# matrix_schematic.net
KiCad netlist of a schematic drawn in EAGLE
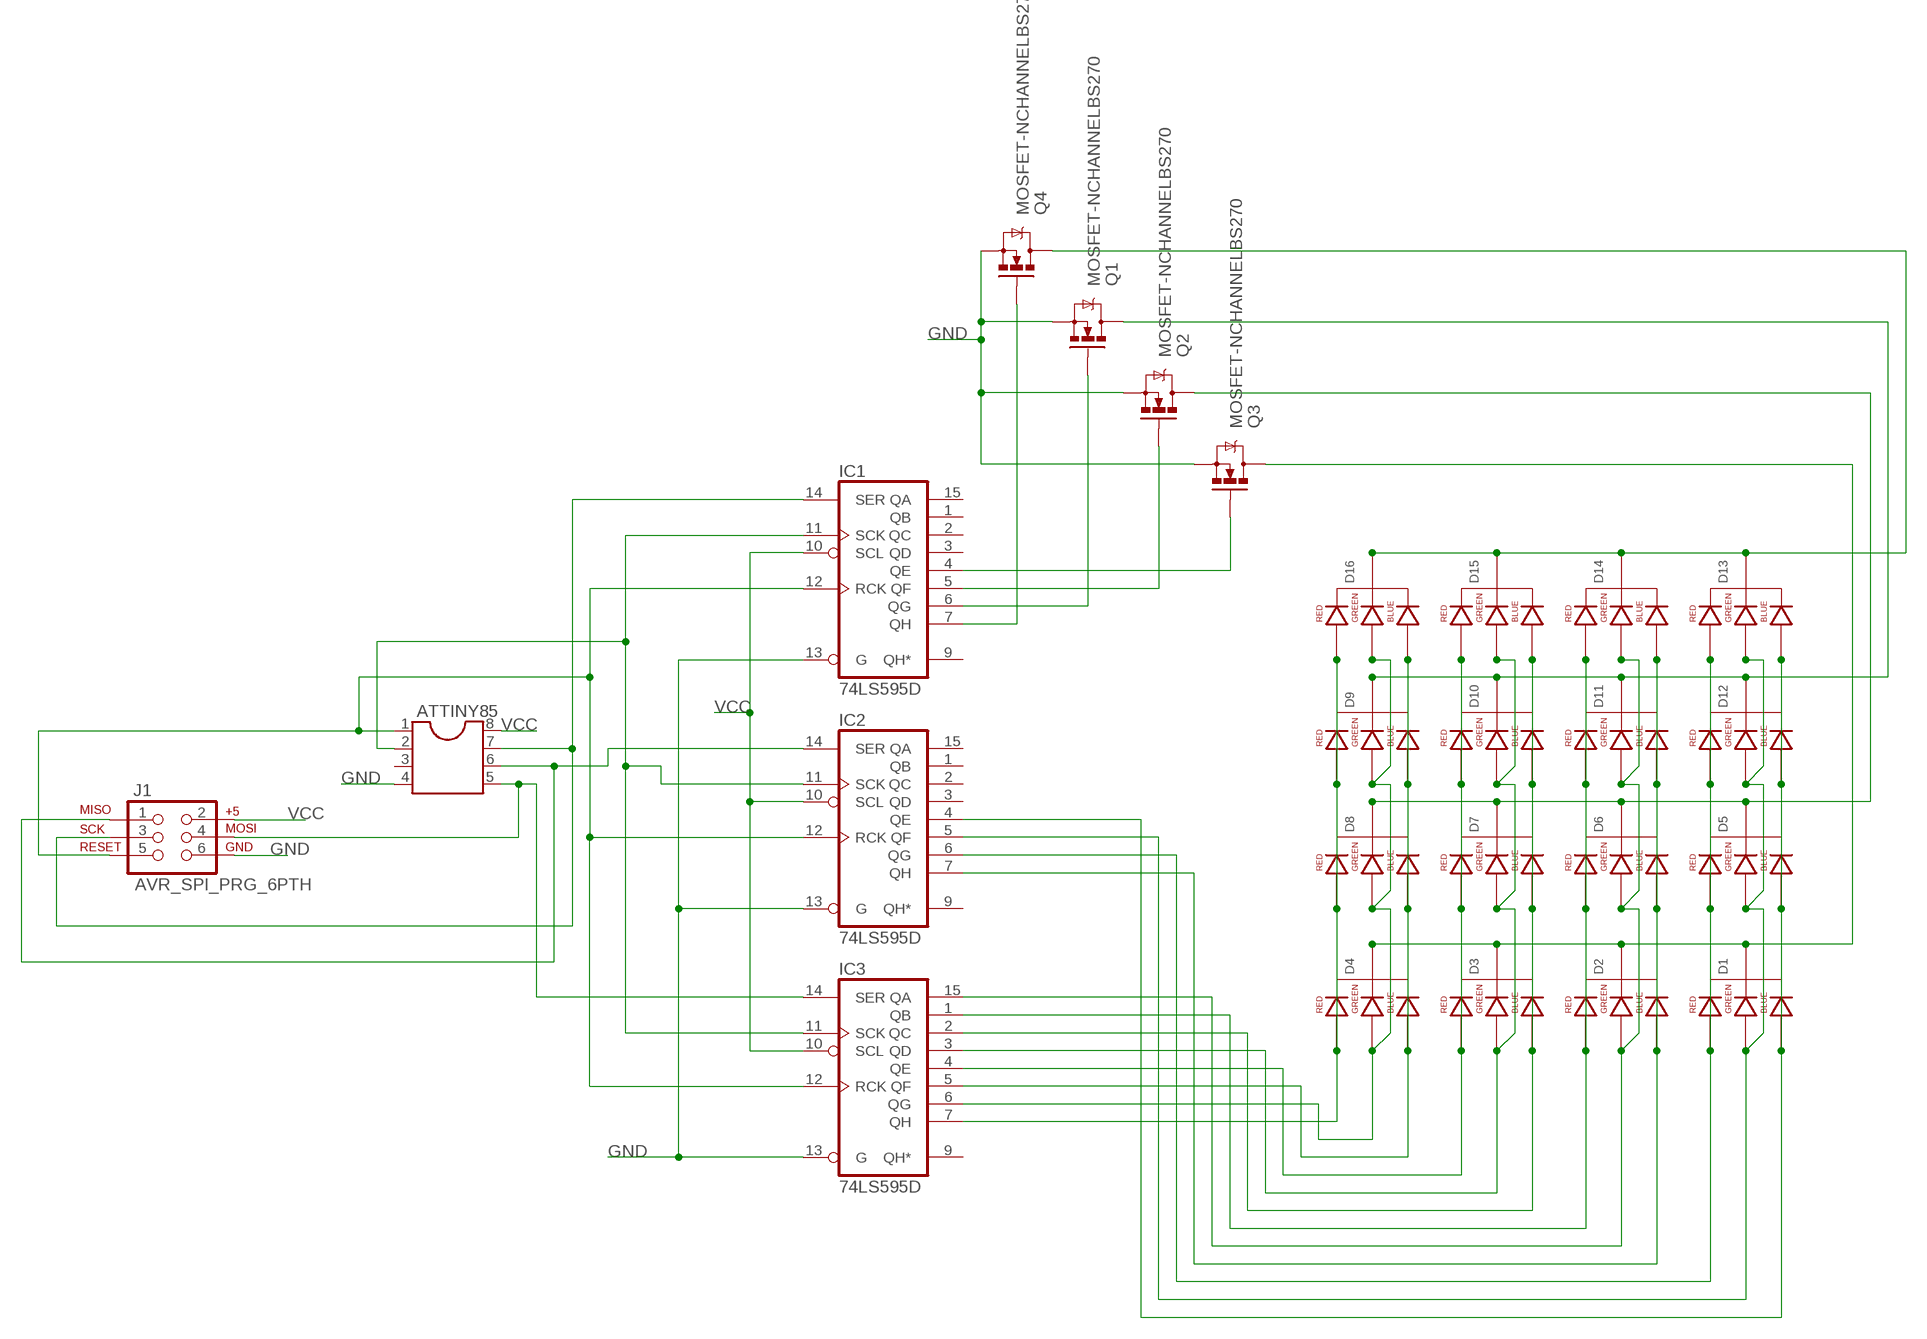
[diagram p0: schematic, sheet 1]

(export (version "E")
  (design (tool "Eeschema 10.0.6"))
  (components
    (comp (ref "ATTINY85")
      (value "DIL8")
      (footprint "eagle-import:DIL08")
      (libsource (lib "eagle-import") (part "DIL8"))
    )
    (comp (ref "D1")
      (value "LED-RGB-CC-THRUDIFFUSE")
      (footprint "eagle-import:LED-RGB-THRU")
      (libsource (lib "eagle-import") (part "LED-RGB-CC-THRUDIFFUSE"))
    )
    (comp (ref "D2")
      (value "LED-RGB-CC-THRUDIFFUSE")
      (footprint "eagle-import:LED-RGB-THRU")
      (libsource (lib "eagle-import") (part "LED-RGB-CC-THRUDIFFUSE"))
    )
    (comp (ref "D3")
      (value "LED-RGB-CC-THRUDIFFUSE")
      (footprint "eagle-import:LED-RGB-THRU")
      (libsource (lib "eagle-import") (part "LED-RGB-CC-THRUDIFFUSE"))
    )
    (comp (ref "D4")
      (value "LED-RGB-CC-THRUDIFFUSE")
      (footprint "eagle-import:LED-RGB-THRU")
      (libsource (lib "eagle-import") (part "LED-RGB-CC-THRUDIFFUSE"))
    )
    (comp (ref "D5")
      (value "LED-RGB-CC-THRUDIFFUSE")
      (footprint "eagle-import:LED-RGB-THRU")
      (libsource (lib "eagle-import") (part "LED-RGB-CC-THRUDIFFUSE"))
    )
    (comp (ref "D6")
      (value "LED-RGB-CC-THRUDIFFUSE")
      (footprint "eagle-import:LED-RGB-THRU")
      (libsource (lib "eagle-import") (part "LED-RGB-CC-THRUDIFFUSE"))
    )
    (comp (ref "D7")
      (value "LED-RGB-CC-THRUDIFFUSE")
      (footprint "eagle-import:LED-RGB-THRU")
      (libsource (lib "eagle-import") (part "LED-RGB-CC-THRUDIFFUSE"))
    )
    (comp (ref "D8")
      (value "LED-RGB-CC-THRUDIFFUSE")
      (footprint "eagle-import:LED-RGB-THRU")
      (libsource (lib "eagle-import") (part "LED-RGB-CC-THRUDIFFUSE"))
    )
    (comp (ref "D9")
      (value "LED-RGB-CC-THRUDIFFUSE")
      (footprint "eagle-import:LED-RGB-THRU")
      (libsource (lib "eagle-import") (part "LED-RGB-CC-THRUDIFFUSE"))
    )
    (comp (ref "D10")
      (value "LED-RGB-CC-THRUDIFFUSE")
      (footprint "eagle-import:LED-RGB-THRU")
      (libsource (lib "eagle-import") (part "LED-RGB-CC-THRUDIFFUSE"))
    )
    (comp (ref "D11")
      (value "LED-RGB-CC-THRUDIFFUSE")
      (footprint "eagle-import:LED-RGB-THRU")
      (libsource (lib "eagle-import") (part "LED-RGB-CC-THRUDIFFUSE"))
    )
    (comp (ref "D12")
      (value "LED-RGB-CC-THRUDIFFUSE")
      (footprint "eagle-import:LED-RGB-THRU")
      (libsource (lib "eagle-import") (part "LED-RGB-CC-THRUDIFFUSE"))
    )
    (comp (ref "D13")
      (value "LED-RGB-CC-THRUDIFFUSE")
      (footprint "eagle-import:LED-RGB-THRU")
      (libsource (lib "eagle-import") (part "LED-RGB-CC-THRUDIFFUSE"))
    )
    (comp (ref "D14")
      (value "LED-RGB-CC-THRUDIFFUSE")
      (footprint "eagle-import:LED-RGB-THRU")
      (libsource (lib "eagle-import") (part "LED-RGB-CC-THRUDIFFUSE"))
    )
    (comp (ref "D15")
      (value "LED-RGB-CC-THRUDIFFUSE")
      (footprint "eagle-import:LED-RGB-THRU")
      (libsource (lib "eagle-import") (part "LED-RGB-CC-THRUDIFFUSE"))
    )
    (comp (ref "D16")
      (value "LED-RGB-CC-THRUDIFFUSE")
      (footprint "eagle-import:LED-RGB-THRU")
      (libsource (lib "eagle-import") (part "LED-RGB-CC-THRUDIFFUSE"))
    )
    (comp (ref "IC1")
      (value "74LS595D")
      (footprint "eagle-import:SO16")
      (libsource (lib "eagle-import") (part "74595DLS"))
    )
    (comp (ref "IC2")
      (value "74LS595D")
      (footprint "eagle-import:SO16")
      (libsource (lib "eagle-import") (part "74595DLS"))
    )
    (comp (ref "IC3")
      (value "74LS595D")
      (footprint "eagle-import:SO16")
      (libsource (lib "eagle-import") (part "74595DLS"))
    )
    (comp (ref "J1")
      (value "AVR_SPI_PRG_6PTH")
      (footprint "eagle-import:2X3")
      (libsource (lib "eagle-import") (part "AVR_SPI_PRG_6PTH"))
    )
    (comp (ref "Q1")
      (value "MOSFET-NCHANNELBS270")
      (footprint "eagle-import:TO-92")
      (libsource (lib "eagle-import") (part "MOSFET-NCHANNELBS170"))
    )
    (comp (ref "Q2")
      (value "MOSFET-NCHANNELBS270")
      (footprint "eagle-import:TO-92")
      (libsource (lib "eagle-import") (part "MOSFET-NCHANNELBS170"))
    )
    (comp (ref "Q3")
      (value "MOSFET-NCHANNELBS270")
      (footprint "eagle-import:TO-92")
      (libsource (lib "eagle-import") (part "MOSFET-NCHANNELBS170"))
    )
    (comp (ref "Q4")
      (value "MOSFET-NCHANNELBS270")
      (footprint "eagle-import:TO-92")
      (libsource (lib "eagle-import") (part "MOSFET-NCHANNELBS170"))
    )
  )
  (nets
    (net (code "1") (name "/GND") (class "Default")
      (node (ref "ATTINY85") (pin "4") (pinfunction "4_4") (pintype "passive"))
      (node (ref "IC1") (pin "13") (pinfunction "G_13") (pintype "input"))
      (node (ref "IC2") (pin "13") (pinfunction "G_13") (pintype "input"))
      (node (ref "IC3") (pin "13") (pinfunction "G_13") (pintype "input"))
      (node (ref "J1") (pin "6") (pinfunction "6_6") (pintype "passive"))
      (node (ref "Q1") (pin "3") (pinfunction "S_3") (pintype "passive"))
      (node (ref "Q2") (pin "3") (pinfunction "S_3") (pintype "passive"))
      (node (ref "Q3") (pin "3") (pinfunction "S_3") (pintype "passive"))
      (node (ref "Q4") (pin "3") (pinfunction "S_3") (pintype "passive"))
    )
    (net (code "2") (name "/VCC") (class "Default")
      (node (ref "ATTINY85") (pin "8") (pinfunction "8_8") (pintype "passive"))
      (node (ref "IC1") (pin "10") (pinfunction "SCL_10") (pintype "input"))
      (node (ref "IC2") (pin "10") (pinfunction "SCL_10") (pintype "input"))
      (node (ref "IC3") (pin "10") (pinfunction "SCL_10") (pintype "input"))
      (node (ref "J1") (pin "2") (pinfunction "2_2") (pintype "passive"))
    )
    (net (code "3") (name "Net-(D1-BLUE_CATHODE)") (class "Default")
      (node (ref "D1") (pin "4") (pinfunction "BLUE_CATHODE_4") (pintype "bidirectional"))
      (node (ref "D12") (pin "4") (pinfunction "BLUE_CATHODE_4") (pintype "bidirectional"))
      (node (ref "D13") (pin "4") (pinfunction "BLUE_CATHODE_4") (pintype "bidirectional"))
      (node (ref "D5") (pin "4") (pinfunction "BLUE_CATHODE_4") (pintype "bidirectional"))
      (node (ref "IC2") (pin "4") (pinfunction "QE_4") (pintype "tri_state"))
    )
    (net (code "4") (name "Net-(D1-CATHODE)") (class "Default")
      (node (ref "D1") (pin "2") (pinfunction "CATHODE_2") (pintype "bidirectional"))
      (node (ref "D2") (pin "2") (pinfunction "CATHODE_2") (pintype "bidirectional"))
      (node (ref "D3") (pin "2") (pinfunction "CATHODE_2") (pintype "bidirectional"))
      (node (ref "D4") (pin "2") (pinfunction "CATHODE_2") (pintype "bidirectional"))
      (node (ref "Q3") (pin "1") (pinfunction "D_1") (pintype "passive"))
    )
    (net (code "5") (name "Net-(D1-GREEN_CATHODE)") (class "Default")
      (node (ref "D1") (pin "3") (pinfunction "GREEN_CATHODE_3") (pintype "bidirectional"))
      (node (ref "D12") (pin "3") (pinfunction "GREEN_CATHODE_3") (pintype "bidirectional"))
      (node (ref "D13") (pin "3") (pinfunction "GREEN_CATHODE_3") (pintype "bidirectional"))
      (node (ref "D5") (pin "3") (pinfunction "GREEN_CATHODE_3") (pintype "bidirectional"))
      (node (ref "IC2") (pin "5") (pinfunction "QF_5") (pintype "tri_state"))
    )
    (net (code "6") (name "Net-(D1-RED_CATHODE)") (class "Default")
      (node (ref "D1") (pin "1") (pinfunction "RED_CATHODE_1") (pintype "bidirectional"))
      (node (ref "D12") (pin "1") (pinfunction "RED_CATHODE_1") (pintype "bidirectional"))
      (node (ref "D13") (pin "1") (pinfunction "RED_CATHODE_1") (pintype "bidirectional"))
      (node (ref "D5") (pin "1") (pinfunction "RED_CATHODE_1") (pintype "bidirectional"))
      (node (ref "IC2") (pin "6") (pinfunction "QG_6") (pintype "tri_state"))
    )
    (net (code "7") (name "Net-(D5-CATHODE)") (class "Default")
      (node (ref "D5") (pin "2") (pinfunction "CATHODE_2") (pintype "bidirectional"))
      (node (ref "D6") (pin "2") (pinfunction "CATHODE_2") (pintype "bidirectional"))
      (node (ref "D7") (pin "2") (pinfunction "CATHODE_2") (pintype "bidirectional"))
      (node (ref "D8") (pin "2") (pinfunction "CATHODE_2") (pintype "bidirectional"))
      (node (ref "Q2") (pin "1") (pinfunction "D_1") (pintype "passive"))
    )
    (net (code "8") (name "Net-(D10-BLUE_CATHODE)") (class "Default")
      (node (ref "D10") (pin "4") (pinfunction "BLUE_CATHODE_4") (pintype "bidirectional"))
      (node (ref "D15") (pin "4") (pinfunction "BLUE_CATHODE_4") (pintype "bidirectional"))
      (node (ref "D3") (pin "4") (pinfunction "BLUE_CATHODE_4") (pintype "bidirectional"))
      (node (ref "D7") (pin "4") (pinfunction "BLUE_CATHODE_4") (pintype "bidirectional"))
      (node (ref "IC3") (pin "2") (pinfunction "QC_2") (pintype "tri_state"))
    )
    (net (code "9") (name "Net-(D10-CATHODE)") (class "Default")
      (node (ref "D10") (pin "2") (pinfunction "CATHODE_2") (pintype "bidirectional"))
      (node (ref "D11") (pin "2") (pinfunction "CATHODE_2") (pintype "bidirectional"))
      (node (ref "D12") (pin "2") (pinfunction "CATHODE_2") (pintype "bidirectional"))
      (node (ref "D9") (pin "2") (pinfunction "CATHODE_2") (pintype "bidirectional"))
      (node (ref "Q1") (pin "1") (pinfunction "D_1") (pintype "passive"))
    )
    (net (code "10") (name "Net-(D10-GREEN_CATHODE)") (class "Default")
      (node (ref "D10") (pin "3") (pinfunction "GREEN_CATHODE_3") (pintype "bidirectional"))
      (node (ref "D15") (pin "3") (pinfunction "GREEN_CATHODE_3") (pintype "bidirectional"))
      (node (ref "D3") (pin "3") (pinfunction "GREEN_CATHODE_3") (pintype "bidirectional"))
      (node (ref "D7") (pin "3") (pinfunction "GREEN_CATHODE_3") (pintype "bidirectional"))
      (node (ref "IC3") (pin "3") (pinfunction "QD_3") (pintype "tri_state"))
    )
    (net (code "11") (name "Net-(D10-RED_CATHODE)") (class "Default")
      (node (ref "D10") (pin "1") (pinfunction "RED_CATHODE_1") (pintype "bidirectional"))
      (node (ref "D15") (pin "1") (pinfunction "RED_CATHODE_1") (pintype "bidirectional"))
      (node (ref "D3") (pin "1") (pinfunction "RED_CATHODE_1") (pintype "bidirectional"))
      (node (ref "D7") (pin "1") (pinfunction "RED_CATHODE_1") (pintype "bidirectional"))
      (node (ref "IC3") (pin "4") (pinfunction "QE_4") (pintype "tri_state"))
    )
    (net (code "12") (name "Net-(D11-BLUE_CATHODE)") (class "Default")
      (node (ref "D11") (pin "4") (pinfunction "BLUE_CATHODE_4") (pintype "bidirectional"))
      (node (ref "D14") (pin "4") (pinfunction "BLUE_CATHODE_4") (pintype "bidirectional"))
      (node (ref "D2") (pin "4") (pinfunction "BLUE_CATHODE_4") (pintype "bidirectional"))
      (node (ref "D6") (pin "4") (pinfunction "BLUE_CATHODE_4") (pintype "bidirectional"))
      (node (ref "IC2") (pin "7") (pinfunction "QH_7") (pintype "tri_state"))
    )
    (net (code "13") (name "Net-(D11-GREEN_CATHODE)") (class "Default")
      (node (ref "D11") (pin "3") (pinfunction "GREEN_CATHODE_3") (pintype "bidirectional"))
      (node (ref "D14") (pin "3") (pinfunction "GREEN_CATHODE_3") (pintype "bidirectional"))
      (node (ref "D2") (pin "3") (pinfunction "GREEN_CATHODE_3") (pintype "bidirectional"))
      (node (ref "D6") (pin "3") (pinfunction "GREEN_CATHODE_3") (pintype "bidirectional"))
      (node (ref "IC3") (pin "15") (pinfunction "QA_15") (pintype "tri_state"))
    )
    (net (code "14") (name "Net-(D11-RED_CATHODE)") (class "Default")
      (node (ref "D11") (pin "1") (pinfunction "RED_CATHODE_1") (pintype "bidirectional"))
      (node (ref "D14") (pin "1") (pinfunction "RED_CATHODE_1") (pintype "bidirectional"))
      (node (ref "D2") (pin "1") (pinfunction "RED_CATHODE_1") (pintype "bidirectional"))
      (node (ref "D6") (pin "1") (pinfunction "RED_CATHODE_1") (pintype "bidirectional"))
      (node (ref "IC3") (pin "1") (pinfunction "QB_1") (pintype "tri_state"))
    )
    (net (code "15") (name "Net-(D13-CATHODE)") (class "Default")
      (node (ref "D13") (pin "2") (pinfunction "CATHODE_2") (pintype "bidirectional"))
      (node (ref "D14") (pin "2") (pinfunction "CATHODE_2") (pintype "bidirectional"))
      (node (ref "D15") (pin "2") (pinfunction "CATHODE_2") (pintype "bidirectional"))
      (node (ref "D16") (pin "2") (pinfunction "CATHODE_2") (pintype "bidirectional"))
      (node (ref "Q4") (pin "1") (pinfunction "D_1") (pintype "passive"))
    )
    (net (code "16") (name "Net-(D16-BLUE_CATHODE)") (class "Default")
      (node (ref "D16") (pin "4") (pinfunction "BLUE_CATHODE_4") (pintype "bidirectional"))
      (node (ref "D4") (pin "4") (pinfunction "BLUE_CATHODE_4") (pintype "bidirectional"))
      (node (ref "D8") (pin "4") (pinfunction "BLUE_CATHODE_4") (pintype "bidirectional"))
      (node (ref "D9") (pin "4") (pinfunction "BLUE_CATHODE_4") (pintype "bidirectional"))
      (node (ref "IC3") (pin "5") (pinfunction "QF_5") (pintype "tri_state"))
    )
    (net (code "17") (name "Net-(D16-GREEN_CATHODE)") (class "Default")
      (node (ref "D16") (pin "3") (pinfunction "GREEN_CATHODE_3") (pintype "bidirectional"))
      (node (ref "D4") (pin "3") (pinfunction "GREEN_CATHODE_3") (pintype "bidirectional"))
      (node (ref "D8") (pin "3") (pinfunction "GREEN_CATHODE_3") (pintype "bidirectional"))
      (node (ref "D9") (pin "3") (pinfunction "GREEN_CATHODE_3") (pintype "bidirectional"))
      (node (ref "IC3") (pin "6") (pinfunction "QG_6") (pintype "tri_state"))
    )
    (net (code "18") (name "Net-(D16-RED_CATHODE)") (class "Default")
      (node (ref "D16") (pin "1") (pinfunction "RED_CATHODE_1") (pintype "bidirectional"))
      (node (ref "D4") (pin "1") (pinfunction "RED_CATHODE_1") (pintype "bidirectional"))
      (node (ref "D8") (pin "1") (pinfunction "RED_CATHODE_1") (pintype "bidirectional"))
      (node (ref "D9") (pin "1") (pinfunction "RED_CATHODE_1") (pintype "bidirectional"))
      (node (ref "IC3") (pin "7") (pinfunction "QH_7") (pintype "tri_state"))
    )
    (net (code "19") (name "Net-(IC1A-QE)") (class "Default")
      (node (ref "IC1") (pin "4") (pinfunction "QE_4") (pintype "tri_state"))
      (node (ref "Q3") (pin "2") (pinfunction "G_2") (pintype "passive"))
    )
    (net (code "20") (name "Net-(IC1A-QF)") (class "Default")
      (node (ref "IC1") (pin "5") (pinfunction "QF_5") (pintype "tri_state"))
      (node (ref "Q2") (pin "2") (pinfunction "G_2") (pintype "passive"))
    )
    (net (code "21") (name "Net-(IC1A-QG)") (class "Default")
      (node (ref "IC1") (pin "6") (pinfunction "QG_6") (pintype "tri_state"))
      (node (ref "Q1") (pin "2") (pinfunction "G_2") (pintype "passive"))
    )
    (net (code "22") (name "Net-(IC1A-QH)") (class "Default")
      (node (ref "IC1") (pin "7") (pinfunction "QH_7") (pintype "tri_state"))
      (node (ref "Q4") (pin "2") (pinfunction "G_2") (pintype "passive"))
    )
    (net (code "23") (name "Net-(IC1A-RCK)") (class "Default")
      (node (ref "ATTINY85") (pin "1") (pinfunction "1_1") (pintype "passive"))
      (node (ref "IC1") (pin "12") (pinfunction "RCK_12") (pintype "input"))
      (node (ref "IC2") (pin "12") (pinfunction "RCK_12") (pintype "input"))
      (node (ref "IC3") (pin "12") (pinfunction "RCK_12") (pintype "input"))
      (node (ref "J1") (pin "5") (pinfunction "5_5") (pintype "passive"))
    )
    (net (code "24") (name "Net-(IC1A-SCK)") (class "Default")
      (node (ref "ATTINY85") (pin "2") (pinfunction "2_2") (pintype "passive"))
      (node (ref "IC1") (pin "11") (pinfunction "SCK_11") (pintype "input"))
      (node (ref "IC2") (pin "11") (pinfunction "SCK_11") (pintype "input"))
      (node (ref "IC3") (pin "11") (pinfunction "SCK_11") (pintype "input"))
    )
    (net (code "25") (name "Net-(IC1A-SER)") (class "Default")
      (node (ref "ATTINY85") (pin "7") (pinfunction "7_7") (pintype "passive"))
      (node (ref "IC1") (pin "14") (pinfunction "SER_14") (pintype "input"))
      (node (ref "J1") (pin "3") (pinfunction "3_3") (pintype "passive"))
    )
    (net (code "26") (name "Net-(IC2A-SER)") (class "Default")
      (node (ref "ATTINY85") (pin "6") (pinfunction "6_6") (pintype "passive"))
      (node (ref "IC2") (pin "14") (pinfunction "SER_14") (pintype "input"))
      (node (ref "J1") (pin "1") (pinfunction "1_1") (pintype "passive"))
    )
    (net (code "27") (name "Net-(IC3A-SER)") (class "Default")
      (node (ref "ATTINY85") (pin "5") (pinfunction "5_5") (pintype "passive"))
      (node (ref "IC3") (pin "14") (pinfunction "SER_14") (pintype "input"))
      (node (ref "J1") (pin "4") (pinfunction "4_4") (pintype "passive"))
    )
    (net (code "28") (name "unconnected-(ATTINY85-Pad3)") (class "Default")
      (node (ref "ATTINY85") (pin "3") (pinfunction "3_3") (pintype "passive"))
    )
    (net (code "29") (name "unconnected-(IC1A-QA-Pad15)") (class "Default")
      (node (ref "IC1") (pin "15") (pinfunction "QA_15") (pintype "tri_state"))
    )
    (net (code "30") (name "unconnected-(IC1A-QB-Pad1)") (class "Default")
      (node (ref "IC1") (pin "1") (pinfunction "QB_1") (pintype "tri_state"))
    )
    (net (code "31") (name "unconnected-(IC1A-QC-Pad2)") (class "Default")
      (node (ref "IC1") (pin "2") (pinfunction "QC_2") (pintype "tri_state"))
    )
    (net (code "32") (name "unconnected-(IC1A-QD-Pad3)") (class "Default")
      (node (ref "IC1") (pin "3") (pinfunction "QD_3") (pintype "tri_state"))
    )
    (net (code "33") (name "unconnected-(IC1A-QH*-Pad9)") (class "Default")
      (node (ref "IC1") (pin "9") (pinfunction "QH*_9") (pintype "tri_state"))
    )
    (net (code "34") (name "unconnected-(IC2A-QA-Pad15)") (class "Default")
      (node (ref "IC2") (pin "15") (pinfunction "QA_15") (pintype "tri_state"))
    )
    (net (code "35") (name "unconnected-(IC2A-QB-Pad1)") (class "Default")
      (node (ref "IC2") (pin "1") (pinfunction "QB_1") (pintype "tri_state"))
    )
    (net (code "36") (name "unconnected-(IC2A-QC-Pad2)") (class "Default")
      (node (ref "IC2") (pin "2") (pinfunction "QC_2") (pintype "tri_state"))
    )
    (net (code "37") (name "unconnected-(IC2A-QD-Pad3)") (class "Default")
      (node (ref "IC2") (pin "3") (pinfunction "QD_3") (pintype "tri_state"))
    )
    (net (code "38") (name "unconnected-(IC2A-QH*-Pad9)") (class "Default")
      (node (ref "IC2") (pin "9") (pinfunction "QH*_9") (pintype "tri_state"))
    )
    (net (code "39") (name "unconnected-(IC3A-QH*-Pad9)") (class "Default")
      (node (ref "IC3") (pin "9") (pinfunction "QH*_9") (pintype "tri_state"))
    )
  )
)
